# eeZeePower.net
KiCad netlist of a schematic drawn in EAGLE
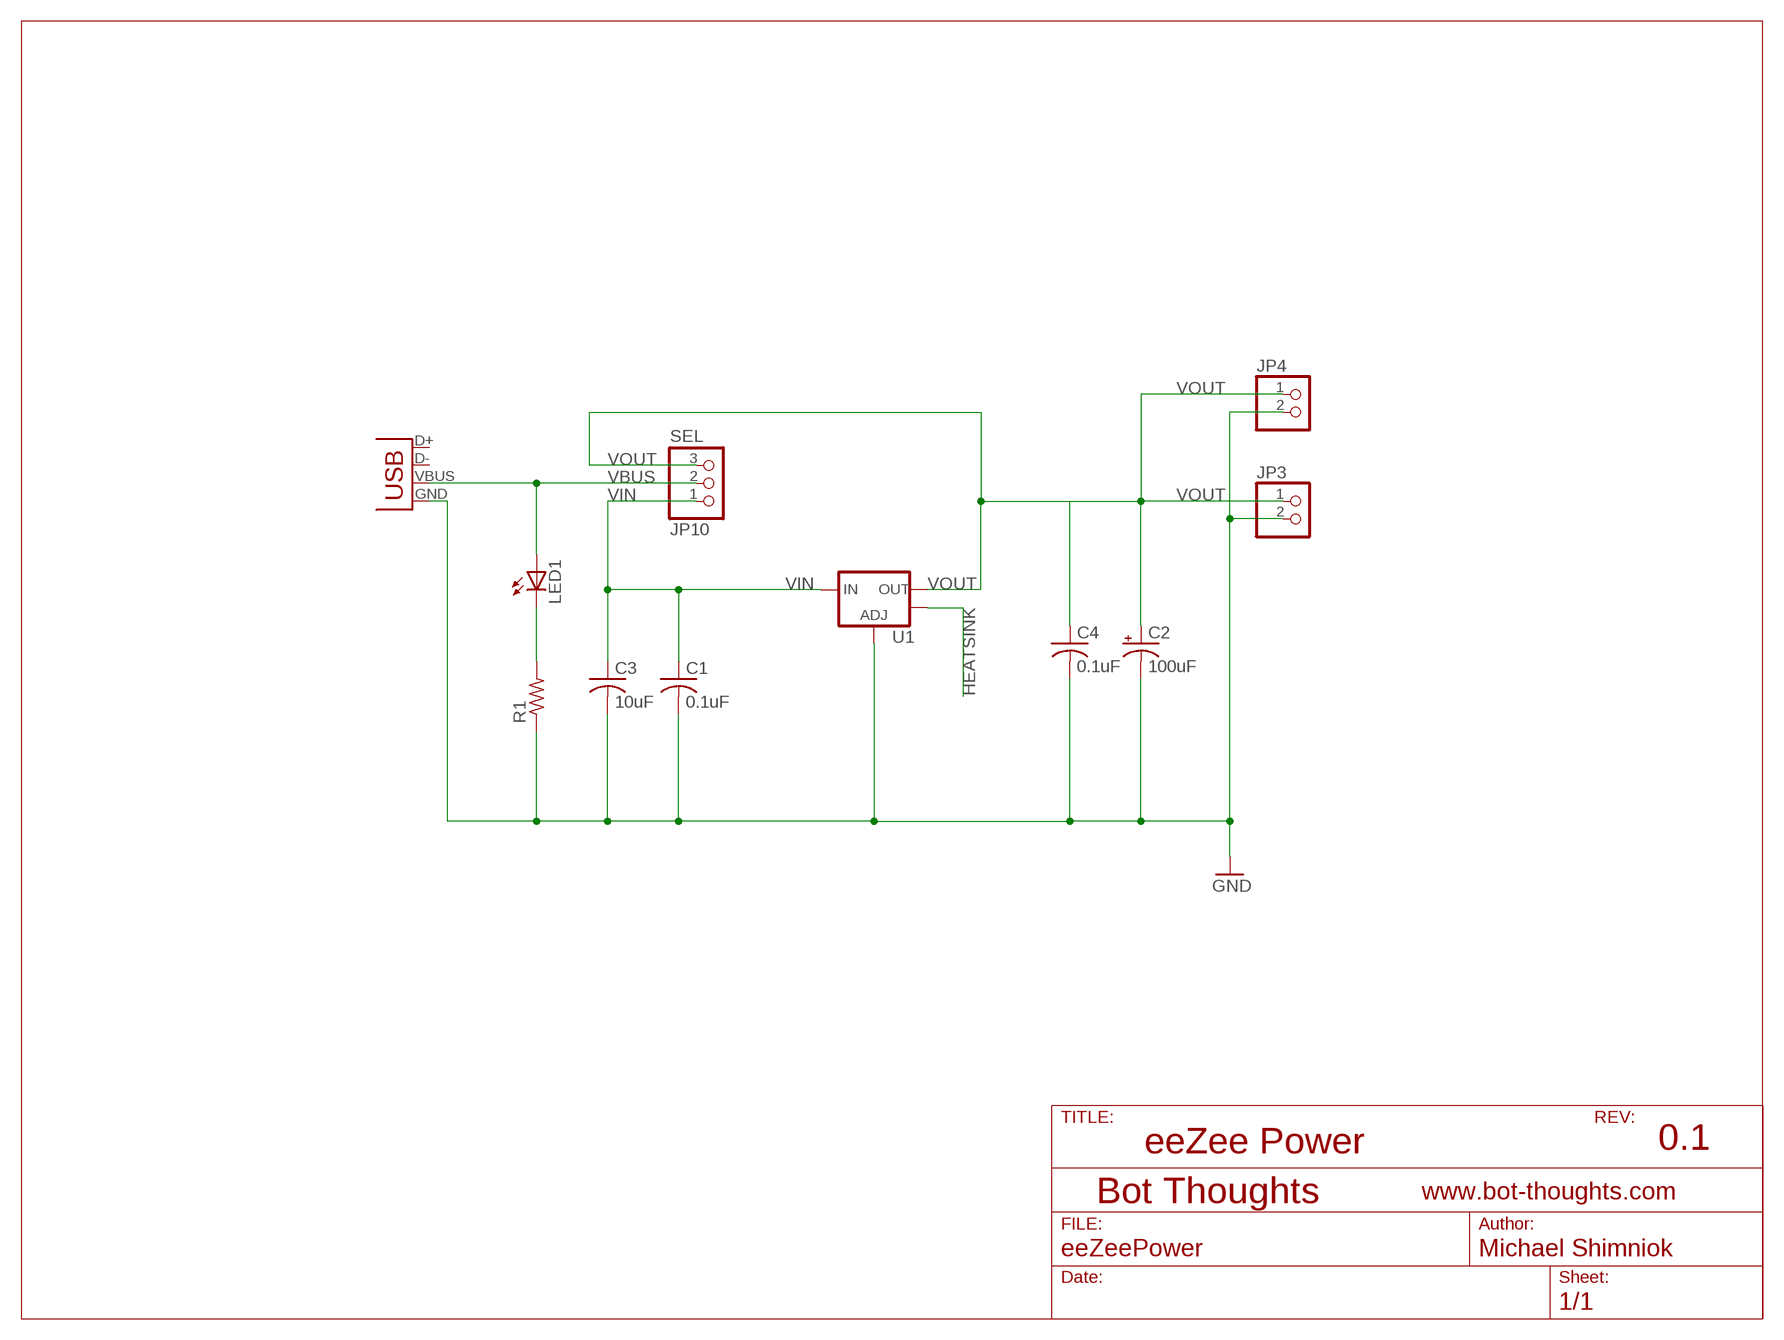
[diagram p0: schematic, sheet 1]

(export (version "E")
  (design (tool "Eeschema 10.0.6"))
  (components
    (comp (ref "C1")
      (value "0.1uF")
      (footprint "eagle-import:C0603")
      (libsource (lib "eagle-import") (part "C-USC0603"))
    )
    (comp (ref "C2")
      (value "100uF")
      (footprint "eagle-import:SMC_B")
      (libsource (lib "eagle-import") (part "CPOL-USSMCB"))
    )
    (comp (ref "C3")
      (value "10uF")
      (footprint "eagle-import:C0603")
      (libsource (lib "eagle-import") (part "C-USC0603"))
    )
    (comp (ref "C4")
      (value "0.1uF")
      (footprint "eagle-import:C0603")
      (libsource (lib "eagle-import") (part "C-USC0603"))
    )
    (comp (ref "JP1")
      (value "USBSMD")
      (footprint "eagle-import:USB-MINIB")
      (libsource (lib "eagle-import") (part "USBSMD"))
    )
    (comp (ref "JP3")
      (value "PINHD-1X02_2.54-S")
      (footprint "eagle-import:1X02-S")
      (libsource (lib "eagle-import") (part "PINHD-1X02_2.54-S"))
    )
    (comp (ref "JP4")
      (value "PINHD-1X02_2.54-S")
      (footprint "eagle-import:1X02-S")
      (libsource (lib "eagle-import") (part "PINHD-1X02_2.54-S"))
    )
    (comp (ref "JP10")
      (value "SEL")
      (footprint "eagle-import:1X03-S")
      (libsource (lib "eagle-import") (part "PINHD-1X03_2.54-S"))
    )
    (comp (ref "LED1")
      (value "LEDCHIPLED_0805")
      (footprint "eagle-import:CHIPLED_0805")
      (libsource (lib "eagle-import") (part "LEDCHIPLED_0805"))
    )
    (comp (ref "R1")
      (value "R-US_R0603")
      (footprint "eagle-import:R0603")
      (libsource (lib "eagle-import") (part "R-US_R0603"))
    )
    (comp (ref "U1")
      (value "V_REG_LM1117SOT223")
      (footprint "eagle-import:SOT223")
      (libsource (lib "eagle-import") (part "V_REG_LM1117SOT223"))
    )
  )
  (nets
    (net (code "1") (name "/HEATSINK") (class "Default")
      (node (ref "U1") (pin "4") (pinfunction "OUT_4") (pintype "output"))
    )
    (net (code "2") (name "/VBUS") (class "Default")
      (node (ref "JP1") (pin "VBUS") (pinfunction "VBUS_VBUS") (pintype "bidirectional"))
      (node (ref "JP10") (pin "2") (pinfunction "2_2") (pintype "passive"))
      (node (ref "LED1") (pin "A") (pinfunction "A_A") (pintype "passive"))
    )
    (net (code "3") (name "/VIN") (class "Default")
      (node (ref "C1") (pin "1") (pinfunction "1_1") (pintype "passive"))
      (node (ref "C3") (pin "1") (pinfunction "1_1") (pintype "passive"))
      (node (ref "JP10") (pin "1") (pinfunction "1_1") (pintype "passive"))
      (node (ref "U1") (pin "3") (pinfunction "IN_3") (pintype "input"))
    )
    (net (code "4") (name "/VOUT") (class "Default")
      (node (ref "C2") (pin "+") (pinfunction "+_+") (pintype "passive"))
      (node (ref "C4") (pin "1") (pinfunction "1_1") (pintype "passive"))
      (node (ref "JP10") (pin "3") (pinfunction "3_3") (pintype "passive"))
      (node (ref "JP3") (pin "1") (pinfunction "1_1") (pintype "passive"))
      (node (ref "JP4") (pin "1") (pinfunction "1_1") (pintype "passive"))
      (node (ref "U1") (pin "2") (pinfunction "OUT_2") (pintype "output"))
    )
    (net (code "5") (name "GND") (class "Default")
      (node (ref "C1") (pin "2") (pinfunction "2_2") (pintype "passive"))
      (node (ref "C2") (pin "-") (pinfunction "-_-") (pintype "passive"))
      (node (ref "C3") (pin "2") (pinfunction "2_2") (pintype "passive"))
      (node (ref "C4") (pin "2") (pinfunction "2_2") (pintype "passive"))
      (node (ref "JP1") (pin "GND") (pinfunction "GND_GND") (pintype "bidirectional"))
      (node (ref "JP3") (pin "2") (pinfunction "2_2") (pintype "passive"))
      (node (ref "JP4") (pin "2") (pinfunction "2_2") (pintype "passive"))
      (node (ref "R1") (pin "1") (pinfunction "1_1") (pintype "passive"))
      (node (ref "U1") (pin "1") (pinfunction "ADJ_1") (pintype "input"))
    )
    (net (code "6") (name "Net-(LED1-PadC)") (class "Default")
      (node (ref "LED1") (pin "C") (pinfunction "C_C") (pintype "passive"))
      (node (ref "R1") (pin "2") (pinfunction "2_2") (pintype "passive"))
    )
    (net (code "7") (name "unconnected-(JP1-PadD+)") (class "Default")
      (node (ref "JP1") (pin "D+") (pinfunction "D+_D+") (pintype "bidirectional"))
    )
    (net (code "8") (name "unconnected-(JP1-PadD-)") (class "Default")
      (node (ref "JP1") (pin "D-") (pinfunction "D-_D-") (pintype "bidirectional"))
    )
  )
)
